# CT310_V1_0.net
KiCad netlist of a schematic drawn in Altium Designer
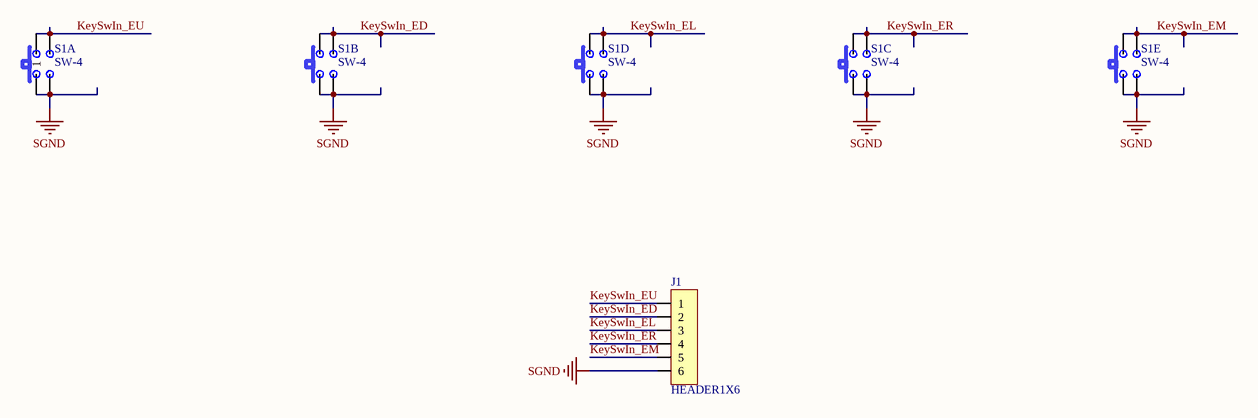
[diagram p0: CT310高端控制盒方向组合按键电路V1.0.SchDoc]

(export (version "E")
  (design (tool "Eeschema 10.0.6"))
  (components
    (comp (ref "J1")
      (value "HEADER1X6")
      (footprint "ZH1X6WT-1.5")
      (libsource (lib "Connector Class") (part "HEADER1X6"))
    )
    (comp (ref "S1")
      (value "SW-4")
      (footprint "SW-MEC-5")
      (libsource (lib "Passive Components Class") (part "SW-4"))
    )
  )
  (nets
    (net (code "1") (name "/KeySwIn_ED") (class "Default")
      (node (ref "J1") (pin "2") (pinfunction "2_2") (pintype "passive"))
      (node (ref "S1") (pin "4") (pintype "passive"))
    )
    (net (code "2") (name "/KeySwIn_EL") (class "Default")
      (node (ref "J1") (pin "3") (pinfunction "3_3") (pintype "passive"))
      (node (ref "S1") (pin "8") (pintype "passive"))
    )
    (net (code "3") (name "/KeySwIn_EM") (class "Default")
      (node (ref "J1") (pin "5") (pinfunction "5_5") (pintype "passive"))
      (node (ref "S1") (pin "10") (pintype "passive"))
    )
    (net (code "4") (name "/KeySwIn_ER") (class "Default")
      (node (ref "J1") (pin "4") (pinfunction "4_4") (pintype "passive"))
      (node (ref "S1") (pin "6") (pintype "passive"))
    )
    (net (code "5") (name "/KeySwIn_EU") (class "Default")
      (node (ref "J1") (pin "1") (pinfunction "1_1") (pintype "passive"))
      (node (ref "S1") (pin "2") (pintype "passive"))
    )
    (net (code "6") (name "SGND") (class "Default")
      (node (ref "J1") (pin "6") (pinfunction "6_6") (pintype "passive"))
      (node (ref "S1") (pin "1") (pintype "passive"))
      (node (ref "S1") (pin "3") (pintype "passive"))
      (node (ref "S1") (pin "5") (pintype "passive"))
      (node (ref "S1") (pin "7") (pintype "passive"))
      (node (ref "S1") (pin "9") (pintype "passive"))
    )
  )
)
